# sparkfun-samd21-mini-breakout-v10.net
KiCad netlist of a schematic drawn in EAGLE
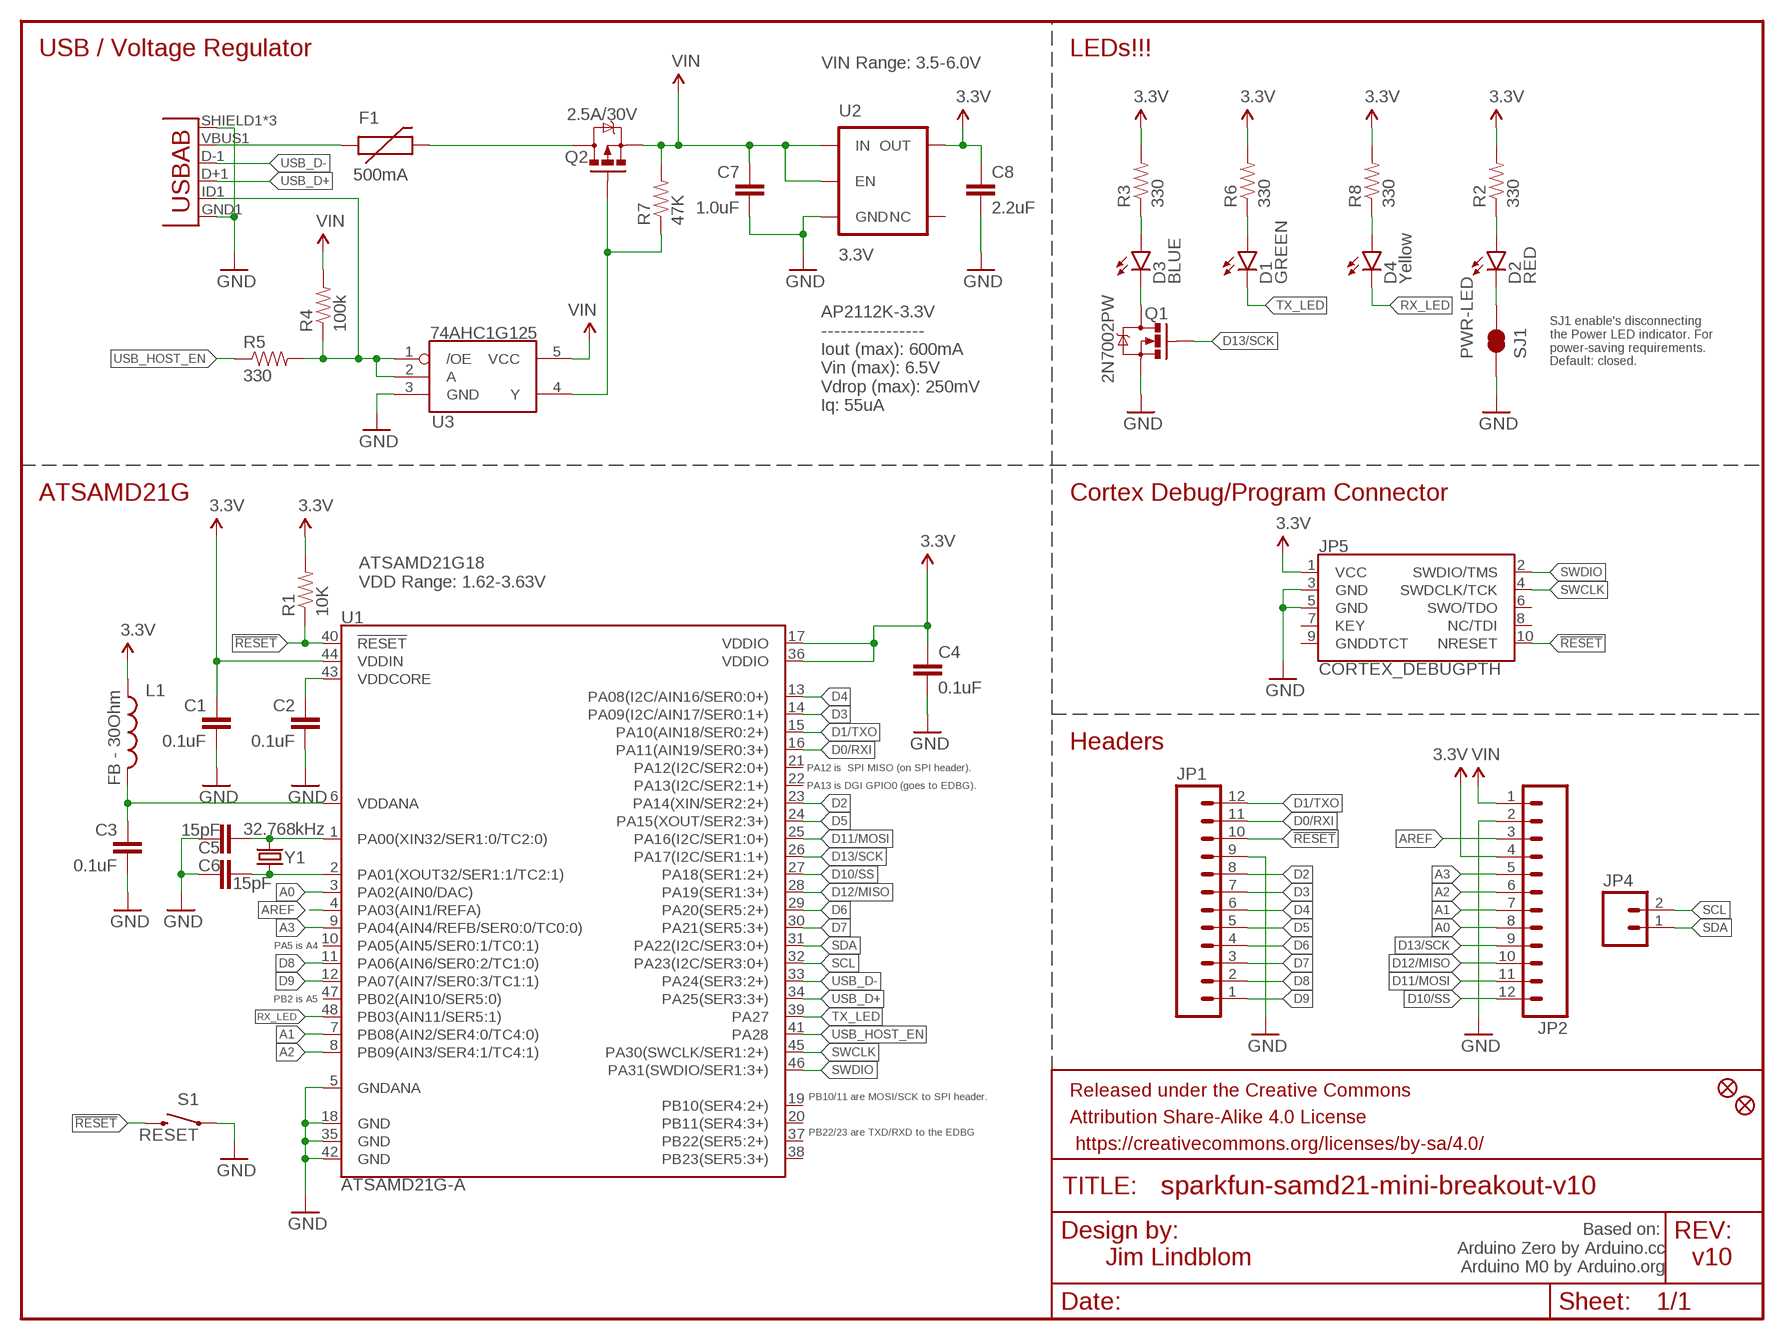
[diagram p0: schematic, sheet 1]

(export (version "E")
  (design (tool "Eeschema 10.0.6"))
  (components
    (comp (ref "C1")
      (value "0.1uF")
      (footprint "eagle-import:0402-CAP")
      (libsource (lib "eagle-import") (part "0.1UF-16V(+-10%)(0402)"))
    )
    (comp (ref "C2")
      (value "0.1uF")
      (footprint "eagle-import:0402-CAP")
      (libsource (lib "eagle-import") (part "0.1UF-16V(+-10%)(0402)"))
    )
    (comp (ref "C3")
      (value "0.1uF")
      (footprint "eagle-import:0402-CAP")
      (libsource (lib "eagle-import") (part "0.1UF-16V(+-10%)(0402)"))
    )
    (comp (ref "C4")
      (value "0.1uF")
      (footprint "eagle-import:0402-CAP")
      (libsource (lib "eagle-import") (part "0.1UF-16V(+-10%)(0402)"))
    )
    (comp (ref "C5")
      (value "15pF")
      (footprint "eagle-import:0402-CAP")
      (libsource (lib "eagle-import") (part "15PF-50V(+-5%)(0402)"))
    )
    (comp (ref "C6")
      (value "15pF")
      (footprint "eagle-import:0402-CAP")
      (libsource (lib "eagle-import") (part "15PF-50V(+-5%)(0402)"))
    )
    (comp (ref "C7")
      (value "1.0uF")
      (footprint "eagle-import:0805-CAP")
      (libsource (lib "eagle-import") (part "1.0UF-25V-+80/-20(0805){dblquote}"))
    )
    (comp (ref "C8")
      (value "2.2uF")
      (footprint "eagle-import:0603-CAP")
      (libsource (lib "eagle-import") (part "2.2UF-10V-20%(0603)"))
    )
    (comp (ref "D1")
      (value "GREEN")
      (footprint "eagle-import:LED-0603")
      (libsource (lib "eagle-import") (part "LED-GREEN0603"))
    )
    (comp (ref "D2")
      (value "RED")
      (footprint "eagle-import:LED-0603")
      (libsource (lib "eagle-import") (part "LED-RED0603"))
    )
    (comp (ref "D3")
      (value "BLUE")
      (footprint "eagle-import:LED-0603")
      (libsource (lib "eagle-import") (part "LED-BLUE0603"))
    )
    (comp (ref "D4")
      (value "Yellow")
      (footprint "eagle-import:LED-0603")
      (libsource (lib "eagle-import") (part "LED-YELLOW0603"))
    )
    (comp (ref "F1")
      (value "500mA")
      (footprint "eagle-import:PTC-1206")
      (libsource (lib "eagle-import") (part "PTCSMD"))
    )
    (comp (ref "FID1")
      (value "FIDUCIAL1X2")
      (footprint "eagle-import:FIDUCIAL-1X2")
      (libsource (lib "eagle-import") (part "FIDUCIAL1X2"))
    )
    (comp (ref "FID2")
      (value "FIDUCIAL1X2")
      (footprint "eagle-import:FIDUCIAL-1X2")
      (libsource (lib "eagle-import") (part "FIDUCIAL1X2"))
    )
    (comp (ref "FRAME1")
      (value "FRAME-LETTER")
      (footprint "eagle-import:CREATIVE_COMMONS")
      (libsource (lib "eagle-import") (part "FRAME-LETTER"))
    )
    (comp (ref "JP1")
      (value "M12NO_SILK")
      (footprint "eagle-import:1X12_NO_SILK")
      (libsource (lib "eagle-import") (part "M12NO_SILK"))
    )
    (comp (ref "JP2")
      (value "M12NO_SILK")
      (footprint "eagle-import:1X12_NO_SILK")
      (libsource (lib "eagle-import") (part "M12NO_SILK"))
    )
    (comp (ref "JP3")
      (value "USB-ABCONN-11794")
      (footprint "eagle-import:USB-AB-MICRO-SMD_V03")
      (libsource (lib "eagle-import") (part "USB-ABCONN-11794"))
    )
    (comp (ref "JP4")
      (value "M021X02_NO_SILK")
      (footprint "eagle-import:1X02_NO_SILK")
      (libsource (lib "eagle-import") (part "M021X02_NO_SILK"))
    )
    (comp (ref "JP5")
      (value "CORTEX_DEBUGPTH")
      (footprint "eagle-import:2X5-PTH-1.27MM")
      (libsource (lib "eagle-import") (part "CORTEX_DEBUGPTH"))
    )
    (comp (ref "L1")
      (value "FB - 30Ohm")
      (footprint "eagle-import:0603")
      (libsource (lib "eagle-import") (part "INDUCTOR0603"))
    )
    (comp (ref "Q1")
      (value "2N7002PW")
      (footprint "eagle-import:SOT323")
      (libsource (lib "eagle-import") (part "MOSFET-NCHANNEL2N7002PW"))
    )
    (comp (ref "Q2")
      (value "2.5A/30V")
      (footprint "eagle-import:SOT23-3")
      (libsource (lib "eagle-import") (part "MOSFET-PCHANNELDMG2307L"))
    )
    (comp (ref "R1")
      (value "10K")
      (footprint "eagle-import:0603-RES")
      (libsource (lib "eagle-import") (part "10KOHM-1/10W-1%(0603)0603"))
    )
    (comp (ref "R2")
      (value "330")
      (footprint "eagle-import:0603-RES")
      (libsource (lib "eagle-import") (part "330OHM1/10W1%(0603)"))
    )
    (comp (ref "R3")
      (value "330")
      (footprint "eagle-import:0603-RES")
      (libsource (lib "eagle-import") (part "330OHM1/10W1%(0603)"))
    )
    (comp (ref "R4")
      (value "100k")
      (footprint "eagle-import:0603-RES")
      (libsource (lib "eagle-import") (part "100KOHM-1/10W-1%(0603)"))
    )
    (comp (ref "R5")
      (value "330")
      (footprint "eagle-import:0603-RES")
      (libsource (lib "eagle-import") (part "330OHM1/10W1%(0603)"))
    )
    (comp (ref "R6")
      (value "330")
      (footprint "eagle-import:0603-RES")
      (libsource (lib "eagle-import") (part "330OHM1/10W1%(0603)"))
    )
    (comp (ref "R7")
      (value "47K")
      (footprint "eagle-import:0603-RES")
      (libsource (lib "eagle-import") (part "47KOHM1/10W1%(0603)"))
    )
    (comp (ref "R8")
      (value "330")
      (footprint "eagle-import:0603-RES")
      (libsource (lib "eagle-import") (part "330OHM1/10W1%(0603)"))
    )
    (comp (ref "S1")
      (value "RESET")
      (footprint "eagle-import:TACTILE_SWITCH_SMD_4.6X2.8MM")
      (libsource (lib "eagle-import") (part "SWITCH-MOMENTARY-2SMD-4.6X2.8MM"))
    )
    (comp (ref "SJ1")
      (value "PWR-LED")
      (footprint "eagle-import:PAD-JUMPER-2-NC_BY_TRACE_NO_SILK")
      (libsource (lib "eagle-import") (part "JUMPER-PAD-2-NC_BY_TRACENO_SILK"))
    )
    (comp (ref "U1")
      (value "ATSAMD21G-A")
      (footprint "eagle-import:TQFP-48")
      (libsource (lib "eagle-import") (part "ATSAMD21G-A"))
    )
    (comp (ref "U2")
      (value "3.3V")
      (footprint "eagle-import:SOT23-5")
      (libsource (lib "eagle-import") (part "V_REG_AP2112K-3.3V"))
    )
    (comp (ref "U3")
      (value "74AHC1G125")
      (footprint "eagle-import:SOT23-5")
      (libsource (lib "eagle-import") (part "74AHC1G125"))
    )
    (comp (ref "Y1")
      (value "32.768kHz")
      (footprint "eagle-import:CRYSTAL-SMD-3.2X1.5MM")
      (libsource (lib "eagle-import") (part "CRYSTAL3.2X1.5MM"))
    )
  )
  (nets
    (net (code "1") (name "/~{RESET}") (class "Default")
      (node (ref "JP1") (pin "10") (pinfunction "10_10") (pintype "passive"))
      (node (ref "JP5") (pin "10") (pinfunction "NRESET_10") (pintype "bidirectional"))
      (node (ref "R1") (pin "1") (pinfunction "1_1") (pintype "passive"))
      (node (ref "S1") (pin "3") (pinfunction "2_3") (pintype "passive"))
      (node (ref "S1") (pin "4") (pinfunction "2_4") (pintype "passive"))
      (node (ref "U1") (pin "40") (pinfunction "~{RESET}_40") (pintype "bidirectional"))
    )
    (net (code "2") (name "3.3V") (class "Default")
      (node (ref "C1") (pin "1") (pinfunction "1_1") (pintype "passive"))
      (node (ref "C4") (pin "1") (pinfunction "1_1") (pintype "passive"))
      (node (ref "C8") (pin "1") (pinfunction "1_1") (pintype "passive"))
      (node (ref "JP2") (pin "4") (pinfunction "4_4") (pintype "passive"))
      (node (ref "JP5") (pin "1") (pinfunction "VCC_1") (pintype "bidirectional"))
      (node (ref "L1") (pin "1") (pinfunction "1_1") (pintype "passive"))
      (node (ref "R1") (pin "2") (pinfunction "2_2") (pintype "passive"))
      (node (ref "R2") (pin "2") (pinfunction "2_2") (pintype "passive"))
      (node (ref "R3") (pin "2") (pinfunction "2_2") (pintype "passive"))
      (node (ref "R6") (pin "2") (pinfunction "2_2") (pintype "passive"))
      (node (ref "R8") (pin "2") (pinfunction "2_2") (pintype "passive"))
      (node (ref "U1") (pin "17") (pinfunction "VDDIO_17") (pintype "bidirectional"))
      (node (ref "U1") (pin "36") (pinfunction "VDDIO_36") (pintype "bidirectional"))
      (node (ref "U1") (pin "44") (pinfunction "VDDIN_44") (pintype "bidirectional"))
      (node (ref "U2") (pin "5") (pinfunction "OUT_5") (pintype "passive"))
    )
    (net (code "3") (name "A0") (class "Default")
      (node (ref "JP2") (pin "8") (pinfunction "8_8") (pintype "passive"))
      (node (ref "U1") (pin "3") (pinfunction "PA02(AIN0/DAC)_3") (pintype "bidirectional"))
    )
    (net (code "4") (name "A1") (class "Default")
      (node (ref "JP2") (pin "7") (pinfunction "7_7") (pintype "passive"))
      (node (ref "U1") (pin "7") (pinfunction "PB08(AIN2/SER4:0/TC4:0)_7") (pintype "bidirectional"))
    )
    (net (code "5") (name "A2") (class "Default")
      (node (ref "JP2") (pin "6") (pinfunction "6_6") (pintype "passive"))
      (node (ref "U1") (pin "8") (pinfunction "PB09(AIN3/SER4:1/TC4:1)_8") (pintype "bidirectional"))
    )
    (net (code "6") (name "A3") (class "Default")
      (node (ref "JP2") (pin "5") (pinfunction "5_5") (pintype "passive"))
      (node (ref "U1") (pin "9") (pinfunction "PA04(AIN4/REFB/SER0:0/TC0:0)_9") (pintype "bidirectional"))
    )
    (net (code "7") (name "AREF") (class "Default")
      (node (ref "JP2") (pin "3") (pinfunction "3_3") (pintype "passive"))
      (node (ref "U1") (pin "4") (pinfunction "PA03(AIN1/REFA)_4") (pintype "bidirectional"))
    )
    (net (code "8") (name "D0{slash}RXI") (class "Default")
      (node (ref "JP1") (pin "11") (pinfunction "11_11") (pintype "passive"))
      (node (ref "U1") (pin "16") (pinfunction "PA11(AIN19/SER0:3+)_16") (pintype "bidirectional"))
    )
    (net (code "9") (name "D1{slash}TXO") (class "Default")
      (node (ref "JP1") (pin "12") (pinfunction "12_12") (pintype "passive"))
      (node (ref "U1") (pin "15") (pinfunction "PA10(AIN18/SER0:2+)_15") (pintype "bidirectional"))
    )
    (net (code "10") (name "D2") (class "Default")
      (node (ref "JP1") (pin "8") (pinfunction "8_8") (pintype "passive"))
      (node (ref "U1") (pin "23") (pinfunction "PA14(XIN/SER2:2+)_23") (pintype "bidirectional"))
    )
    (net (code "11") (name "D3") (class "Default")
      (node (ref "JP1") (pin "7") (pinfunction "7_7") (pintype "passive"))
      (node (ref "U1") (pin "14") (pinfunction "PA09(I2C/AIN17/SER0:1+)_14") (pintype "bidirectional"))
    )
    (net (code "12") (name "D4") (class "Default")
      (node (ref "JP1") (pin "6") (pinfunction "6_6") (pintype "passive"))
      (node (ref "U1") (pin "13") (pinfunction "PA08(I2C/AIN16/SER0:0+)_13") (pintype "bidirectional"))
    )
    (net (code "13") (name "D5") (class "Default")
      (node (ref "JP1") (pin "5") (pinfunction "5_5") (pintype "passive"))
      (node (ref "U1") (pin "24") (pinfunction "PA15(XOUT/SER2:3+)_24") (pintype "bidirectional"))
    )
    (net (code "14") (name "D6") (class "Default")
      (node (ref "JP1") (pin "4") (pinfunction "4_4") (pintype "passive"))
      (node (ref "U1") (pin "29") (pinfunction "PA20(SER5:2+)_29") (pintype "bidirectional"))
    )
    (net (code "15") (name "D7") (class "Default")
      (node (ref "JP1") (pin "3") (pinfunction "3_3") (pintype "passive"))
      (node (ref "U1") (pin "30") (pinfunction "PA21(SER5:3+)_30") (pintype "bidirectional"))
    )
    (net (code "16") (name "D8") (class "Default")
      (node (ref "JP1") (pin "2") (pinfunction "2_2") (pintype "passive"))
      (node (ref "U1") (pin "11") (pinfunction "PA06(AIN6/SER0:2/TC1:0)_11") (pintype "bidirectional"))
    )
    (net (code "17") (name "D9") (class "Default")
      (node (ref "JP1") (pin "1") (pinfunction "1_1") (pintype "passive"))
      (node (ref "U1") (pin "12") (pinfunction "PA07(AIN7/SER0:3/TC1:1)_12") (pintype "bidirectional"))
    )
    (net (code "18") (name "D10{slash}SS") (class "Default")
      (node (ref "JP2") (pin "12") (pinfunction "12_12") (pintype "passive"))
      (node (ref "U1") (pin "27") (pinfunction "PA18(SER1:2+)_27") (pintype "bidirectional"))
    )
    (net (code "19") (name "D11{slash}MOSI") (class "Default")
      (node (ref "JP2") (pin "11") (pinfunction "11_11") (pintype "passive"))
      (node (ref "U1") (pin "25") (pinfunction "PA16(I2C/SER1:0+)_25") (pintype "bidirectional"))
    )
    (net (code "20") (name "D12{slash}MISO") (class "Default")
      (node (ref "JP2") (pin "10") (pinfunction "10_10") (pintype "passive"))
      (node (ref "U1") (pin "28") (pinfunction "PA19(SER1:3+)_28") (pintype "bidirectional"))
    )
    (net (code "21") (name "D13{slash}SCK") (class "Default")
      (node (ref "JP2") (pin "9") (pinfunction "9_9") (pintype "passive"))
      (node (ref "Q1") (pin "1") (pinfunction "G_1") (pintype "passive"))
      (node (ref "U1") (pin "26") (pinfunction "PA17(I2C/SER1:1+)_26") (pintype "bidirectional"))
    )
    (net (code "22") (name "GND") (class "Default")
      (node (ref "C1") (pin "2") (pinfunction "2_2") (pintype "passive"))
      (node (ref "C2") (pin "2") (pinfunction "2_2") (pintype "passive"))
      (node (ref "C3") (pin "2") (pinfunction "2_2") (pintype "passive"))
      (node (ref "C4") (pin "2") (pinfunction "2_2") (pintype "passive"))
      (node (ref "C5") (pin "1") (pinfunction "1_1") (pintype "passive"))
      (node (ref "C6") (pin "2") (pinfunction "2_2") (pintype "passive"))
      (node (ref "C7") (pin "2") (pinfunction "2_2") (pintype "passive"))
      (node (ref "C8") (pin "2") (pinfunction "2_2") (pintype "passive"))
      (node (ref "JP1") (pin "9") (pinfunction "9_9") (pintype "passive"))
      (node (ref "JP2") (pin "2") (pinfunction "2_2") (pintype "passive"))
      (node (ref "JP3") (pin "GND1") (pinfunction "GND_GND1") (pintype "bidirectional"))
      (node (ref "JP3") (pin "SHIELD1") (pinfunction "SHIELD_SHIELD1") (pintype "bidirectional"))
      (node (ref "JP3") (pin "SHIELD2") (pinfunction "SHIELD_SHIELD2") (pintype "bidirectional"))
      (node (ref "JP3") (pin "SHIELD3") (pinfunction "SHIELD_SHIELD3") (pintype "bidirectional"))
      (node (ref "JP5") (pin "3") (pinfunction "GND_3") (pintype "bidirectional"))
      (node (ref "JP5") (pin "5") (pinfunction "GND_5") (pintype "bidirectional"))
      (node (ref "Q1") (pin "2") (pinfunction "S_2") (pintype "passive"))
      (node (ref "S1") (pin "1") (pinfunction "1_1") (pintype "passive"))
      (node (ref "S1") (pin "2") (pinfunction "1_2") (pintype "passive"))
      (node (ref "SJ1") (pin "1") (pinfunction "1_1") (pintype "passive"))
      (node (ref "U1") (pin "18") (pinfunction "GND_18") (pintype "bidirectional"))
      (node (ref "U1") (pin "35") (pinfunction "GND_35") (pintype "bidirectional"))
      (node (ref "U1") (pin "42") (pinfunction "GND_42") (pintype "bidirectional"))
      (node (ref "U1") (pin "5") (pinfunction "GNDANA_5") (pintype "bidirectional"))
      (node (ref "U2") (pin "2") (pinfunction "GND_2") (pintype "input"))
      (node (ref "U3") (pin "3") (pinfunction "GND_3") (pintype "bidirectional"))
    )
    (net (code "23") (name "Net-(D1-PadA)") (class "Default")
      (node (ref "D1") (pin "A") (pinfunction "A_A") (pintype "passive"))
      (node (ref "R6") (pin "1") (pinfunction "1_1") (pintype "passive"))
    )
    (net (code "24") (name "Net-(D2-PadA)") (class "Default")
      (node (ref "D2") (pin "A") (pinfunction "A_A") (pintype "passive"))
      (node (ref "R2") (pin "1") (pinfunction "1_1") (pintype "passive"))
    )
    (net (code "25") (name "Net-(D2-PadC)") (class "Default")
      (node (ref "D2") (pin "C") (pinfunction "C_C") (pintype "passive"))
      (node (ref "SJ1") (pin "2") (pinfunction "2_2") (pintype "passive"))
    )
    (net (code "26") (name "Net-(D3-PadA)") (class "Default")
      (node (ref "D3") (pin "A") (pinfunction "A_A") (pintype "passive"))
      (node (ref "R3") (pin "1") (pinfunction "1_1") (pintype "passive"))
    )
    (net (code "27") (name "Net-(D4-PadA)") (class "Default")
      (node (ref "D4") (pin "A") (pinfunction "A_A") (pintype "passive"))
      (node (ref "R8") (pin "1") (pinfunction "1_1") (pintype "passive"))
    )
    (net (code "28") (name "Net-(JP3-USBID)") (class "Default")
      (node (ref "JP3") (pin "ID1") (pinfunction "USBID_ID1") (pintype "bidirectional"))
      (node (ref "R4") (pin "1") (pinfunction "1_1") (pintype "passive"))
      (node (ref "R5") (pin "2") (pinfunction "2_2") (pintype "passive"))
      (node (ref "U3") (pin "1") (pinfunction "/OE_1") (pintype "bidirectional"))
      (node (ref "U3") (pin "2") (pinfunction "A_2") (pintype "bidirectional"))
    )
    (net (code "29") (name "Net-(JP3-VBUS)") (class "Default")
      (node (ref "F1") (pin "1") (pinfunction "1_1") (pintype "bidirectional"))
      (node (ref "JP3") (pin "VBUS1") (pinfunction "VBUS_VBUS1") (pintype "bidirectional"))
    )
    (net (code "30") (name "Net-(Q1-D)") (class "Default")
      (node (ref "D3") (pin "C") (pinfunction "C_C") (pintype "passive"))
      (node (ref "Q1") (pin "3") (pinfunction "D_3") (pintype "passive"))
    )
    (net (code "31") (name "Net-(Q2-D)") (class "Default")
      (node (ref "F1") (pin "2") (pinfunction "2_2") (pintype "bidirectional"))
      (node (ref "Q2") (pin "3") (pinfunction "D_3") (pintype "passive"))
    )
    (net (code "32") (name "Net-(Q2-G)") (class "Default")
      (node (ref "Q2") (pin "1") (pinfunction "G_1") (pintype "passive"))
      (node (ref "R7") (pin "1") (pinfunction "1_1") (pintype "passive"))
      (node (ref "U3") (pin "4") (pinfunction "Y_4") (pintype "bidirectional"))
    )
    (net (code "33") (name "Net-(U1-PA00(XIN32{slash}SER1:0{slash}TC2:0))") (class "Default")
      (node (ref "C5") (pin "2") (pinfunction "2_2") (pintype "passive"))
      (node (ref "U1") (pin "1") (pinfunction "PA00(XIN32/SER1:0/TC2:0)_1") (pintype "bidirectional"))
      (node (ref "Y1") (pin "P$2") (pinfunction "2_P$2") (pintype "passive"))
    )
    (net (code "34") (name "Net-(U1-PA01(XOUT32{slash}SER1:1{slash}TC2:1))") (class "Default")
      (node (ref "C6") (pin "1") (pinfunction "1_1") (pintype "passive"))
      (node (ref "U1") (pin "2") (pinfunction "PA01(XOUT32/SER1:1/TC2:1)_2") (pintype "bidirectional"))
      (node (ref "Y1") (pin "P$1") (pinfunction "1_P$1") (pintype "passive"))
    )
    (net (code "35") (name "Net-(U1-VDDANA)") (class "Default")
      (node (ref "C3") (pin "1") (pinfunction "1_1") (pintype "passive"))
      (node (ref "L1") (pin "2") (pinfunction "2_2") (pintype "passive"))
      (node (ref "U1") (pin "6") (pinfunction "VDDANA_6") (pintype "bidirectional"))
    )
    (net (code "36") (name "Net-(U1-VDDCORE)") (class "Default")
      (node (ref "C2") (pin "1") (pinfunction "1_1") (pintype "passive"))
      (node (ref "U1") (pin "43") (pinfunction "VDDCORE_43") (pintype "bidirectional"))
    )
    (net (code "37") (name "RX_LED") (class "Default")
      (node (ref "D4") (pin "C") (pinfunction "C_C") (pintype "passive"))
      (node (ref "U1") (pin "48") (pinfunction "PB03(AIN11/SER5:1)_48") (pintype "bidirectional"))
    )
    (net (code "38") (name "SCL") (class "Default")
      (node (ref "JP4") (pin "2") (pinfunction "2_2") (pintype "passive"))
      (node (ref "U1") (pin "32") (pinfunction "PA23(I2C/SER3:0+)_32") (pintype "bidirectional"))
    )
    (net (code "39") (name "SDA") (class "Default")
      (node (ref "JP4") (pin "1") (pinfunction "1_1") (pintype "passive"))
      (node (ref "U1") (pin "31") (pinfunction "PA22(I2C/SER3:0+)_31") (pintype "bidirectional"))
    )
    (net (code "40") (name "SWCLK") (class "Default")
      (node (ref "JP5") (pin "4") (pinfunction "SWDCLK/TCK_4") (pintype "bidirectional"))
      (node (ref "U1") (pin "45") (pinfunction "PA30(SWCLK/SER1:2+)_45") (pintype "bidirectional"))
    )
    (net (code "41") (name "SWDIO") (class "Default")
      (node (ref "JP5") (pin "2") (pinfunction "SWDIO/TMS_2") (pintype "bidirectional"))
      (node (ref "U1") (pin "46") (pinfunction "PA31(SWDIO/SER1:3+)_46") (pintype "bidirectional"))
    )
    (net (code "42") (name "TX_LED") (class "Default")
      (node (ref "D1") (pin "C") (pinfunction "C_C") (pintype "passive"))
      (node (ref "U1") (pin "39") (pinfunction "PA27_39") (pintype "bidirectional"))
    )
    (net (code "43") (name "USB_D+") (class "Default")
      (node (ref "JP3") (pin "D+1") (pinfunction "D+_D+1") (pintype "bidirectional"))
      (node (ref "U1") (pin "34") (pinfunction "PA25(SER3:3+)_34") (pintype "bidirectional"))
    )
    (net (code "44") (name "USB_D-") (class "Default")
      (node (ref "JP3") (pin "D-1") (pinfunction "D-_D-1") (pintype "bidirectional"))
      (node (ref "U1") (pin "33") (pinfunction "PA24(SER3:2+)_33") (pintype "bidirectional"))
    )
    (net (code "45") (name "USB_HOST_EN") (class "Default")
      (node (ref "R5") (pin "1") (pinfunction "1_1") (pintype "passive"))
      (node (ref "U1") (pin "41") (pinfunction "PA28_41") (pintype "bidirectional"))
    )
    (net (code "46") (name "VIN") (class "Default")
      (node (ref "C7") (pin "1") (pinfunction "1_1") (pintype "passive"))
      (node (ref "JP2") (pin "1") (pinfunction "1_1") (pintype "passive"))
      (node (ref "Q2") (pin "2") (pinfunction "S_2") (pintype "passive"))
      (node (ref "R4") (pin "2") (pinfunction "2_2") (pintype "passive"))
      (node (ref "R7") (pin "2") (pinfunction "2_2") (pintype "passive"))
      (node (ref "U2") (pin "1") (pinfunction "IN_1") (pintype "input"))
      (node (ref "U2") (pin "3") (pinfunction "EN_3") (pintype "input"))
      (node (ref "U3") (pin "5") (pinfunction "VCC_5") (pintype "bidirectional"))
    )
    (net (code "47") (name "unconnected-(JP5-GNDDTCT-Pad9)") (class "Default")
      (node (ref "JP5") (pin "9") (pinfunction "GNDDTCT_9") (pintype "bidirectional"))
    )
    (net (code "48") (name "unconnected-(JP5-KEY-Pad7)") (class "Default")
      (node (ref "JP5") (pin "7") (pinfunction "KEY_7") (pintype "bidirectional"))
    )
    (net (code "49") (name "unconnected-(JP5-NC{slash}TDI-Pad8)") (class "Default")
      (node (ref "JP5") (pin "8") (pinfunction "NC/TDI_8") (pintype "bidirectional"))
    )
    (net (code "50") (name "unconnected-(JP5-SWO{slash}TDO-Pad6)") (class "Default")
      (node (ref "JP5") (pin "6") (pinfunction "SWO/TDO_6") (pintype "bidirectional"))
    )
    (net (code "51") (name "unconnected-(U1-PA05(AIN5{slash}SER0:1{slash}TC0:1)-Pad10)") (class "Default")
      (node (ref "U1") (pin "10") (pinfunction "PA05(AIN5/SER0:1/TC0:1)_10") (pintype "bidirectional"))
    )
    (net (code "52") (name "unconnected-(U1-PA12(I2C{slash}SER2:0+)-Pad21)") (class "Default")
      (node (ref "U1") (pin "21") (pinfunction "PA12(I2C/SER2:0+)_21") (pintype "bidirectional"))
    )
    (net (code "53") (name "unconnected-(U1-PA13(I2C{slash}SER2:1+)-Pad22)") (class "Default")
      (node (ref "U1") (pin "22") (pinfunction "PA13(I2C/SER2:1+)_22") (pintype "bidirectional"))
    )
    (net (code "54") (name "unconnected-(U1-PB02(AIN10{slash}SER5:0)-Pad47)") (class "Default")
      (node (ref "U1") (pin "47") (pinfunction "PB02(AIN10/SER5:0)_47") (pintype "bidirectional"))
    )
    (net (code "55") (name "unconnected-(U1-PB10(SER4:2+)-Pad19)") (class "Default")
      (node (ref "U1") (pin "19") (pinfunction "PB10(SER4:2+)_19") (pintype "bidirectional"))
    )
    (net (code "56") (name "unconnected-(U1-PB11(SER4:3+)-Pad20)") (class "Default")
      (node (ref "U1") (pin "20") (pinfunction "PB11(SER4:3+)_20") (pintype "bidirectional"))
    )
    (net (code "57") (name "unconnected-(U1-PB22(SER5:2+)-Pad37)") (class "Default")
      (node (ref "U1") (pin "37") (pinfunction "PB22(SER5:2+)_37") (pintype "bidirectional"))
    )
    (net (code "58") (name "unconnected-(U1-PB23(SER5:3+)-Pad38)") (class "Default")
      (node (ref "U1") (pin "38") (pinfunction "PB23(SER5:3+)_38") (pintype "bidirectional"))
    )
    (net (code "59") (name "unconnected-(U2-NC-Pad4)") (class "Default")
      (node (ref "U2") (pin "4") (pinfunction "NC_4") (pintype "input"))
    )
  )
)
